# 2-DDR2.net
KiCad netlist of a schematic drawn in Altium Designer
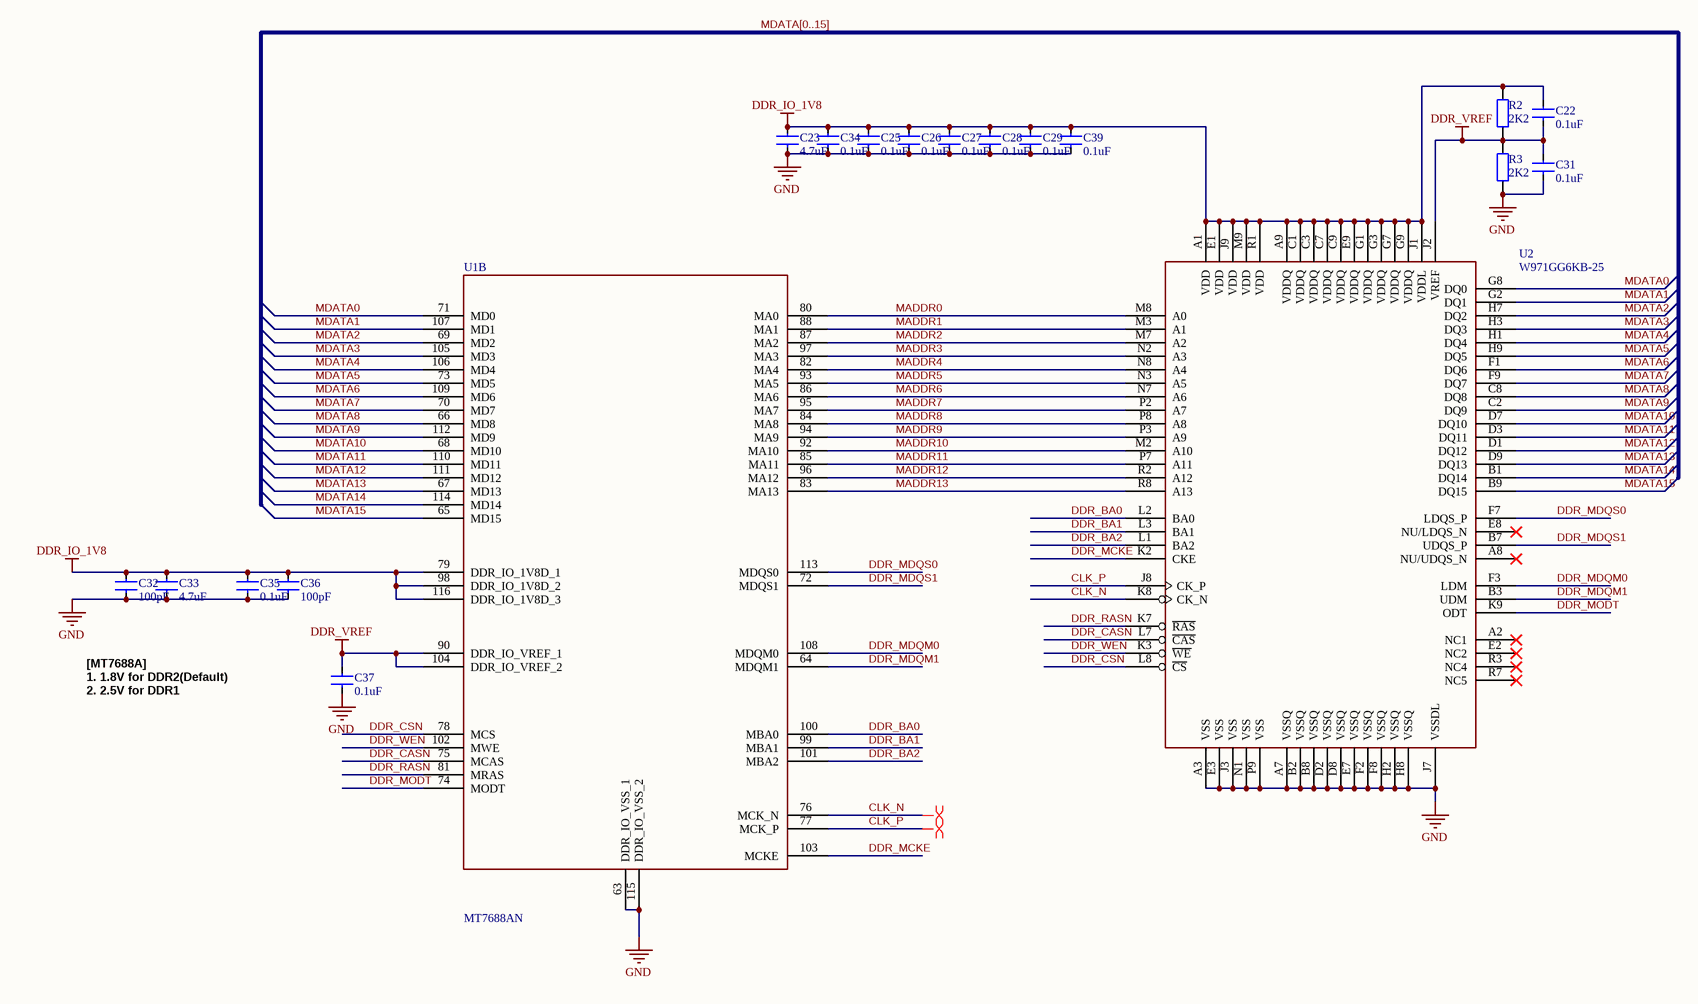
[diagram p0: 2-DDR2.SchDoc]

(export (version "E")
  (design (tool "Eeschema 10.0.6"))
  (components
    (comp (ref "C22")
      (value "0.1uF")
      (footprint "C0402")
      (description "普通小电容")
      (libsource (lib "LIB_MANGO") (part "CAP"))
    )
    (comp (ref "C23")
      (value "4.7uF")
      (footprint "C0402")
      (description "普通小电容")
      (libsource (lib "LIB_MANGO") (part "CAP"))
    )
    (comp (ref "C25")
      (value "0.1uF")
      (footprint "C0402")
      (description "普通小电容")
      (libsource (lib "LIB_MANGO") (part "CAP"))
    )
    (comp (ref "C26")
      (value "0.1uF")
      (footprint "C0402")
      (description "普通小电容")
      (libsource (lib "LIB_MANGO") (part "CAP"))
    )
    (comp (ref "C27")
      (value "0.1uF")
      (footprint "C0402")
      (description "普通小电容")
      (libsource (lib "LIB_MANGO") (part "CAP"))
    )
    (comp (ref "C28")
      (value "0.1uF")
      (footprint "C0402")
      (description "普通小电容")
      (libsource (lib "LIB_MANGO") (part "CAP"))
    )
    (comp (ref "C29")
      (value "0.1uF")
      (footprint "C0402")
      (description "普通小电容")
      (libsource (lib "LIB_MANGO") (part "CAP"))
    )
    (comp (ref "C31")
      (value "0.1uF")
      (footprint "C0402")
      (description "普通小电容")
      (libsource (lib "LIB_MANGO") (part "CAP"))
    )
    (comp (ref "C32")
      (value "100pF")
      (footprint "C0402")
      (description "普通小电容")
      (libsource (lib "LIB_MANGO") (part "CAP"))
    )
    (comp (ref "C33")
      (value "4.7uF")
      (footprint "C0402")
      (description "普通小电容")
      (libsource (lib "LIB_MANGO") (part "CAP"))
    )
    (comp (ref "C34")
      (value "0.1uF")
      (footprint "C0402")
      (description "普通小电容")
      (libsource (lib "LIB_MANGO") (part "CAP"))
    )
    (comp (ref "C35")
      (value "0.1uF")
      (footprint "C0402")
      (description "普通小电容")
      (libsource (lib "LIB_MANGO") (part "CAP"))
    )
    (comp (ref "C36")
      (value "100pF")
      (footprint "C0402")
      (description "普通小电容")
      (libsource (lib "LIB_MANGO") (part "CAP"))
    )
    (comp (ref "C37")
      (value "0.1uF")
      (footprint "C0402")
      (description "普通小电容")
      (libsource (lib "LIB_MANGO") (part "CAP"))
    )
    (comp (ref "C39")
      (value "0.1uF")
      (footprint "C0402")
      (description "普通小电容")
      (libsource (lib "LIB_MANGO") (part "CAP"))
    )
    (comp (ref "R2")
      (value "2K2")
      (footprint "R0402")
      (description "普通电阻")
      (libsource (lib "LIB_MANGO") (part "RES"))
    )
    (comp (ref "R3")
      (value "2K2")
      (footprint "R0402")
      (description "普通电阻")
      (libsource (lib "LIB_MANGO") (part "RES"))
    )
    (comp (ref "U1")
      (value "MT7688AN")
      (footprint "MT7628AN/DRQFN156/SMD/P0.5/12X12")
      (libsource (lib "A") (part "MT7688AN"))
    )
    (comp (ref "U2")
      (value "W971GG6KB-25")
      (footprint "FBGA84-small")
      (description "128MB DDR2 Winbond")
      (libsource (lib "ALL") (part "DDR2_x16_512Gb_2Gb"))
    )
  )
  (nets
    (net (code "1") (name "/CLK_N") (class "Default")
      (node (ref "U1") (pin "76") (pinfunction "MCK_N_76") (pintype "passive"))
      (node (ref "U2") (pin "K8") (pinfunction "CK_N_K8") (pintype "passive"))
    )
    (net (code "2") (name "/CLK_P") (class "Default")
      (node (ref "U1") (pin "77") (pinfunction "MCK_P_77") (pintype "passive"))
      (node (ref "U2") (pin "J8") (pinfunction "CK_P_J8") (pintype "passive"))
    )
    (net (code "3") (name "/DDR_BA0") (class "Default")
      (node (ref "U1") (pin "100") (pinfunction "MBA0_100") (pintype "passive"))
      (node (ref "U2") (pin "L2") (pinfunction "BA0_L2") (pintype "passive"))
    )
    (net (code "4") (name "/DDR_BA1") (class "Default")
      (node (ref "U1") (pin "99") (pinfunction "MBA1_99") (pintype "passive"))
      (node (ref "U2") (pin "L3") (pinfunction "BA1_L3") (pintype "passive"))
    )
    (net (code "5") (name "/DDR_BA2") (class "Default")
      (node (ref "U1") (pin "101") (pinfunction "MBA2_101") (pintype "passive"))
      (node (ref "U2") (pin "L1") (pinfunction "BA2_L1") (pintype "passive"))
    )
    (net (code "6") (name "/DDR_CASN") (class "Default")
      (node (ref "U1") (pin "75") (pinfunction "MCAS_75") (pintype "passive"))
      (node (ref "U2") (pin "L7") (pinfunction "~{CAS}_L7") (pintype "passive"))
    )
    (net (code "7") (name "/DDR_CSN") (class "Default")
      (node (ref "U1") (pin "78") (pinfunction "MCS_78") (pintype "passive"))
      (node (ref "U2") (pin "L8") (pinfunction "~{CS}_L8") (pintype "passive"))
    )
    (net (code "8") (name "/DDR_MCKE") (class "Default")
      (node (ref "U1") (pin "103") (pinfunction "MCKE_103") (pintype "passive"))
      (node (ref "U2") (pin "K2") (pinfunction "CKE_K2") (pintype "passive"))
    )
    (net (code "9") (name "/DDR_MDQM0") (class "Default")
      (node (ref "U1") (pin "108") (pinfunction "MDQM0_108") (pintype "passive"))
      (node (ref "U2") (pin "F3") (pinfunction "LDM_F3") (pintype "passive"))
    )
    (net (code "10") (name "/DDR_MDQM1") (class "Default")
      (node (ref "U1") (pin "64") (pinfunction "MDQM1_64") (pintype "passive"))
      (node (ref "U2") (pin "B3") (pinfunction "UDM_B3") (pintype "passive"))
    )
    (net (code "11") (name "/DDR_MDQS0") (class "Default")
      (node (ref "U1") (pin "113") (pinfunction "MDQS0_113") (pintype "passive"))
      (node (ref "U2") (pin "F7") (pinfunction "LDQS_P_F7") (pintype "passive"))
    )
    (net (code "12") (name "/DDR_MDQS1") (class "Default")
      (node (ref "U1") (pin "72") (pinfunction "MDQS1_72") (pintype "passive"))
      (node (ref "U2") (pin "B7") (pinfunction "UDQS_P_B7") (pintype "passive"))
    )
    (net (code "13") (name "/DDR_MODT") (class "Default")
      (node (ref "U1") (pin "74") (pinfunction "MODT_74") (pintype "passive"))
      (node (ref "U2") (pin "K9") (pinfunction "ODT_K9") (pintype "passive"))
    )
    (net (code "14") (name "/DDR_RASN") (class "Default")
      (node (ref "U1") (pin "81") (pinfunction "MRAS_81") (pintype "passive"))
      (node (ref "U2") (pin "K7") (pinfunction "~{RAS}_K7") (pintype "passive"))
    )
    (net (code "15") (name "/DDR_WEN") (class "Default")
      (node (ref "U1") (pin "102") (pinfunction "MWE_102") (pintype "passive"))
      (node (ref "U2") (pin "K3") (pinfunction "~{WE}_K3") (pintype "passive"))
    )
    (net (code "16") (name "/MADDR0") (class "Default")
      (node (ref "U1") (pin "80") (pinfunction "MA0_80") (pintype "passive"))
      (node (ref "U2") (pin "M8") (pinfunction "A0_M8") (pintype "passive"))
    )
    (net (code "17") (name "/MADDR1") (class "Default")
      (node (ref "U1") (pin "88") (pinfunction "MA1_88") (pintype "passive"))
      (node (ref "U2") (pin "M3") (pinfunction "A1_M3") (pintype "passive"))
    )
    (net (code "18") (name "/MADDR2") (class "Default")
      (node (ref "U1") (pin "87") (pinfunction "MA2_87") (pintype "passive"))
      (node (ref "U2") (pin "M7") (pinfunction "A2_M7") (pintype "passive"))
    )
    (net (code "19") (name "/MADDR3") (class "Default")
      (node (ref "U1") (pin "97") (pinfunction "MA3_97") (pintype "passive"))
      (node (ref "U2") (pin "N2") (pinfunction "A3_N2") (pintype "passive"))
    )
    (net (code "20") (name "/MADDR4") (class "Default")
      (node (ref "U1") (pin "82") (pinfunction "MA4_82") (pintype "passive"))
      (node (ref "U2") (pin "N8") (pinfunction "A4_N8") (pintype "passive"))
    )
    (net (code "21") (name "/MADDR5") (class "Default")
      (node (ref "U1") (pin "93") (pinfunction "MA5_93") (pintype "passive"))
      (node (ref "U2") (pin "N3") (pinfunction "A5_N3") (pintype "passive"))
    )
    (net (code "22") (name "/MADDR6") (class "Default")
      (node (ref "U1") (pin "86") (pinfunction "MA6_86") (pintype "passive"))
      (node (ref "U2") (pin "N7") (pinfunction "A6_N7") (pintype "passive"))
    )
    (net (code "23") (name "/MADDR7") (class "Default")
      (node (ref "U1") (pin "95") (pinfunction "MA7_95") (pintype "passive"))
      (node (ref "U2") (pin "P2") (pinfunction "A7_P2") (pintype "passive"))
    )
    (net (code "24") (name "/MADDR8") (class "Default")
      (node (ref "U1") (pin "84") (pinfunction "MA8_84") (pintype "passive"))
      (node (ref "U2") (pin "P8") (pinfunction "A8_P8") (pintype "passive"))
    )
    (net (code "25") (name "/MADDR9") (class "Default")
      (node (ref "U1") (pin "94") (pinfunction "MA9_94") (pintype "passive"))
      (node (ref "U2") (pin "P3") (pinfunction "A9_P3") (pintype "passive"))
    )
    (net (code "26") (name "/MADDR10") (class "Default")
      (node (ref "U1") (pin "92") (pinfunction "MA10_92") (pintype "passive"))
      (node (ref "U2") (pin "M2") (pinfunction "A10_M2") (pintype "passive"))
    )
    (net (code "27") (name "/MADDR11") (class "Default")
      (node (ref "U1") (pin "85") (pinfunction "MA11_85") (pintype "passive"))
      (node (ref "U2") (pin "P7") (pinfunction "A11_P7") (pintype "passive"))
    )
    (net (code "28") (name "/MADDR12") (class "Default")
      (node (ref "U1") (pin "96") (pinfunction "MA12_96") (pintype "passive"))
      (node (ref "U2") (pin "R2") (pinfunction "A12_R2") (pintype "passive"))
    )
    (net (code "29") (name "/MADDR13") (class "Default")
      (node (ref "U1") (pin "83") (pinfunction "MA13_83") (pintype "passive"))
      (node (ref "U2") (pin "R8") (pinfunction "A13_R8") (pintype "passive"))
    )
    (net (code "30") (name "/MDATA0") (class "Default")
      (node (ref "U1") (pin "71") (pinfunction "MD0_71") (pintype "passive"))
      (node (ref "U2") (pin "G8") (pinfunction "DQ0_G8") (pintype "passive"))
    )
    (net (code "31") (name "/MDATA1") (class "Default")
      (node (ref "U1") (pin "107") (pinfunction "MD1_107") (pintype "passive"))
      (node (ref "U2") (pin "G2") (pinfunction "DQ1_G2") (pintype "passive"))
    )
    (net (code "32") (name "/MDATA2") (class "Default")
      (node (ref "U1") (pin "69") (pinfunction "MD2_69") (pintype "passive"))
      (node (ref "U2") (pin "H7") (pinfunction "DQ2_H7") (pintype "passive"))
    )
    (net (code "33") (name "/MDATA3") (class "Default")
      (node (ref "U1") (pin "105") (pinfunction "MD3_105") (pintype "passive"))
      (node (ref "U2") (pin "H3") (pinfunction "DQ3_H3") (pintype "passive"))
    )
    (net (code "34") (name "/MDATA4") (class "Default")
      (node (ref "U1") (pin "106") (pinfunction "MD4_106") (pintype "passive"))
      (node (ref "U2") (pin "H1") (pinfunction "DQ4_H1") (pintype "passive"))
    )
    (net (code "35") (name "/MDATA5") (class "Default")
      (node (ref "U1") (pin "73") (pinfunction "MD5_73") (pintype "passive"))
      (node (ref "U2") (pin "H9") (pinfunction "DQ5_H9") (pintype "passive"))
    )
    (net (code "36") (name "/MDATA6") (class "Default")
      (node (ref "U1") (pin "109") (pinfunction "MD6_109") (pintype "passive"))
      (node (ref "U2") (pin "F1") (pinfunction "DQ6_F1") (pintype "passive"))
    )
    (net (code "37") (name "/MDATA7") (class "Default")
      (node (ref "U1") (pin "70") (pinfunction "MD7_70") (pintype "passive"))
      (node (ref "U2") (pin "F9") (pinfunction "DQ7_F9") (pintype "passive"))
    )
    (net (code "38") (name "/MDATA8") (class "Default")
      (node (ref "U1") (pin "66") (pinfunction "MD8_66") (pintype "passive"))
      (node (ref "U2") (pin "C8") (pinfunction "DQ8_C8") (pintype "passive"))
    )
    (net (code "39") (name "/MDATA9") (class "Default")
      (node (ref "U1") (pin "112") (pinfunction "MD9_112") (pintype "passive"))
      (node (ref "U2") (pin "C2") (pinfunction "DQ9_C2") (pintype "passive"))
    )
    (net (code "40") (name "/MDATA10") (class "Default")
      (node (ref "U1") (pin "68") (pinfunction "MD10_68") (pintype "passive"))
      (node (ref "U2") (pin "D7") (pinfunction "DQ10_D7") (pintype "passive"))
    )
    (net (code "41") (name "/MDATA11") (class "Default")
      (node (ref "U1") (pin "110") (pinfunction "MD11_110") (pintype "passive"))
      (node (ref "U2") (pin "D3") (pinfunction "DQ11_D3") (pintype "passive"))
    )
    (net (code "42") (name "/MDATA12") (class "Default")
      (node (ref "U1") (pin "111") (pinfunction "MD12_111") (pintype "passive"))
      (node (ref "U2") (pin "D1") (pinfunction "DQ12_D1") (pintype "passive"))
    )
    (net (code "43") (name "/MDATA13") (class "Default")
      (node (ref "U1") (pin "67") (pinfunction "MD13_67") (pintype "passive"))
      (node (ref "U2") (pin "D9") (pinfunction "DQ13_D9") (pintype "passive"))
    )
    (net (code "44") (name "/MDATA14") (class "Default")
      (node (ref "U1") (pin "114") (pinfunction "MD14_114") (pintype "passive"))
      (node (ref "U2") (pin "B1") (pinfunction "DQ14_B1") (pintype "passive"))
    )
    (net (code "45") (name "/MDATA15") (class "Default")
      (node (ref "U1") (pin "65") (pinfunction "MD15_65") (pintype "passive"))
      (node (ref "U2") (pin "B9") (pinfunction "DQ15_B9") (pintype "passive"))
    )
    (net (code "47") (name "DDR_IO_1V8") (class "Default")
      (node (ref "C22") (pin "1") (pinfunction "1_1") (pintype "passive"))
      (node (ref "C23") (pin "1") (pinfunction "1_1") (pintype "passive"))
      (node (ref "C25") (pin "1") (pinfunction "1_1") (pintype "passive"))
      (node (ref "C26") (pin "1") (pinfunction "1_1") (pintype "passive"))
      (node (ref "C27") (pin "1") (pinfunction "1_1") (pintype "passive"))
      (node (ref "C28") (pin "1") (pinfunction "1_1") (pintype "passive"))
      (node (ref "C29") (pin "1") (pinfunction "1_1") (pintype "passive"))
      (node (ref "C32") (pin "1") (pinfunction "1_1") (pintype "passive"))
      (node (ref "C33") (pin "1") (pinfunction "1_1") (pintype "passive"))
      (node (ref "C34") (pin "1") (pinfunction "1_1") (pintype "passive"))
      (node (ref "C35") (pin "1") (pinfunction "1_1") (pintype "passive"))
      (node (ref "C36") (pin "1") (pinfunction "1_1") (pintype "passive"))
      (node (ref "C39") (pin "1") (pinfunction "1_1") (pintype "passive"))
      (node (ref "R2") (pin "2") (pinfunction "2_2") (pintype "passive"))
      (node (ref "U1") (pin "116") (pinfunction "DDR_IO_1V8D_3_116") (pintype "passive"))
      (node (ref "U1") (pin "79") (pinfunction "DDR_IO_1V8D_1_79") (pintype "passive"))
      (node (ref "U1") (pin "98") (pinfunction "DDR_IO_1V8D_2_98") (pintype "passive"))
      (node (ref "U2") (pin "A1") (pinfunction "VDD_A1") (pintype "passive"))
      (node (ref "U2") (pin "A9") (pinfunction "VDDQ_A9") (pintype "passive"))
      (node (ref "U2") (pin "C1") (pinfunction "VDDQ_C1") (pintype "passive"))
      (node (ref "U2") (pin "C3") (pinfunction "VDDQ_C3") (pintype "passive"))
      (node (ref "U2") (pin "C7") (pinfunction "VDDQ_C7") (pintype "passive"))
      (node (ref "U2") (pin "C9") (pinfunction "VDDQ_C9") (pintype "passive"))
      (node (ref "U2") (pin "E1") (pinfunction "VDD_E1") (pintype "passive"))
      (node (ref "U2") (pin "E9") (pinfunction "VDDQ_E9") (pintype "passive"))
      (node (ref "U2") (pin "G1") (pinfunction "VDDQ_G1") (pintype "passive"))
      (node (ref "U2") (pin "G3") (pinfunction "VDDQ_G3") (pintype "passive"))
      (node (ref "U2") (pin "G7") (pinfunction "VDDQ_G7") (pintype "passive"))
      (node (ref "U2") (pin "G9") (pinfunction "VDDQ_G9") (pintype "passive"))
      (node (ref "U2") (pin "J1") (pinfunction "VDDL_J1") (pintype "passive"))
      (node (ref "U2") (pin "J9") (pinfunction "VDD_J9") (pintype "passive"))
      (node (ref "U2") (pin "M9") (pinfunction "VDD_M9") (pintype "passive"))
      (node (ref "U2") (pin "R1") (pinfunction "VDD_R1") (pintype "passive"))
    )
    (net (code "48") (name "DDR_VREF") (class "Default")
      (node (ref "C22") (pin "2") (pinfunction "2_2") (pintype "passive"))
      (node (ref "C31") (pin "1") (pinfunction "1_1") (pintype "passive"))
      (node (ref "C37") (pin "1") (pinfunction "1_1") (pintype "passive"))
      (node (ref "R2") (pin "1") (pinfunction "1_1") (pintype "passive"))
      (node (ref "R3") (pin "2") (pinfunction "2_2") (pintype "passive"))
      (node (ref "U1") (pin "104") (pinfunction "DDR_IO_VREF_2_104") (pintype "passive"))
      (node (ref "U1") (pin "90") (pinfunction "DDR_IO_VREF_1_90") (pintype "passive"))
      (node (ref "U2") (pin "J2") (pinfunction "VREF_J2") (pintype "passive"))
    )
    (net (code "49") (name "GND") (class "Default")
      (node (ref "C23") (pin "2") (pinfunction "2_2") (pintype "passive"))
      (node (ref "C25") (pin "2") (pinfunction "2_2") (pintype "passive"))
      (node (ref "C26") (pin "2") (pinfunction "2_2") (pintype "passive"))
      (node (ref "C27") (pin "2") (pinfunction "2_2") (pintype "passive"))
      (node (ref "C28") (pin "2") (pinfunction "2_2") (pintype "passive"))
      (node (ref "C29") (pin "2") (pinfunction "2_2") (pintype "passive"))
      (node (ref "C31") (pin "2") (pinfunction "2_2") (pintype "passive"))
      (node (ref "C32") (pin "2") (pinfunction "2_2") (pintype "passive"))
      (node (ref "C33") (pin "2") (pinfunction "2_2") (pintype "passive"))
      (node (ref "C34") (pin "2") (pinfunction "2_2") (pintype "passive"))
      (node (ref "C35") (pin "2") (pinfunction "2_2") (pintype "passive"))
      (node (ref "C36") (pin "2") (pinfunction "2_2") (pintype "passive"))
      (node (ref "C37") (pin "2") (pinfunction "2_2") (pintype "passive"))
      (node (ref "C39") (pin "2") (pinfunction "2_2") (pintype "passive"))
      (node (ref "R3") (pin "1") (pinfunction "1_1") (pintype "passive"))
      (node (ref "U1") (pin "115") (pinfunction "DDR_IO_VSS_2_115") (pintype "passive"))
      (node (ref "U1") (pin "63") (pinfunction "DDR_IO_VSS_1_63") (pintype "passive"))
      (node (ref "U2") (pin "A3") (pinfunction "VSS_A3") (pintype "passive"))
      (node (ref "U2") (pin "A7") (pinfunction "VSSQ_A7") (pintype "passive"))
      (node (ref "U2") (pin "B2") (pinfunction "VSSQ_B2") (pintype "passive"))
      (node (ref "U2") (pin "B8") (pinfunction "VSSQ_B8") (pintype "passive"))
      (node (ref "U2") (pin "D2") (pinfunction "VSSQ_D2") (pintype "passive"))
      (node (ref "U2") (pin "D8") (pinfunction "VSSQ_D8") (pintype "passive"))
      (node (ref "U2") (pin "E3") (pinfunction "VSS_E3") (pintype "passive"))
      (node (ref "U2") (pin "E7") (pinfunction "VSSQ_E7") (pintype "passive"))
      (node (ref "U2") (pin "F2") (pinfunction "VSSQ_F2") (pintype "passive"))
      (node (ref "U2") (pin "F8") (pinfunction "VSSQ_F8") (pintype "passive"))
      (node (ref "U2") (pin "H2") (pinfunction "VSSQ_H2") (pintype "passive"))
      (node (ref "U2") (pin "H8") (pinfunction "VSSQ_H8") (pintype "passive"))
      (node (ref "U2") (pin "J3") (pinfunction "VSS_J3") (pintype "passive"))
      (node (ref "U2") (pin "J7") (pinfunction "VSSDL_J7") (pintype "passive"))
      (node (ref "U2") (pin "N1") (pinfunction "VSS_N1") (pintype "passive"))
      (node (ref "U2") (pin "P9") (pinfunction "VSS_P9") (pintype "passive"))
    )
    (net (code "50") (name "unconnected-(U2-NC1-PadA2)") (class "Default")
      (node (ref "U2") (pin "A2") (pinfunction "NC1_A2") (pintype "passive+no_connect"))
    )
    (net (code "51") (name "unconnected-(U2-NC2-PadE2)") (class "Default")
      (node (ref "U2") (pin "E2") (pinfunction "NC2_E2") (pintype "passive+no_connect"))
    )
    (net (code "52") (name "unconnected-(U2-NC4-PadR3)") (class "Default")
      (node (ref "U2") (pin "R3") (pinfunction "NC4_R3") (pintype "passive+no_connect"))
    )
    (net (code "53") (name "unconnected-(U2-NC5-PadR7)") (class "Default")
      (node (ref "U2") (pin "R7") (pinfunction "NC5_R7") (pintype "passive+no_connect"))
    )
    (net (code "54") (name "unconnected-(U2-NU{slash}LDQS_N-PadE8)") (class "Default")
      (node (ref "U2") (pin "E8") (pinfunction "NU/LDQS_N_E8") (pintype "passive+no_connect"))
    )
    (net (code "55") (name "unconnected-(U2-NU{slash}UDQS_N-PadA8)") (class "Default")
      (node (ref "U2") (pin "A8") (pinfunction "NU/UDQS_N_A8") (pintype "passive+no_connect"))
    )
  )
)
